# blinds.net
KiCad netlist of a schematic drawn in Altium Designer
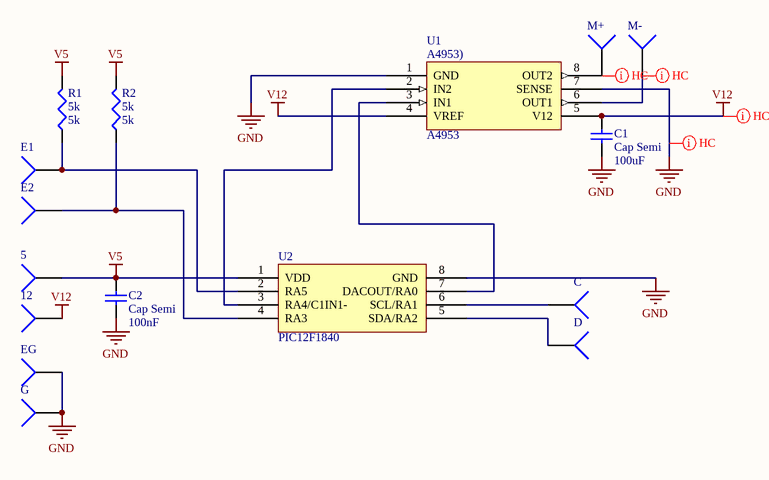
[diagram p0: blinds.SchDoc]

(export (version "E")
  (design (tool "Eeschema 10.0.6"))
  (components
    (comp (ref "5")
      (value "Socket")
      (footprint "PIN1L")
      (fields (field (name "PUBLISHER") "Altium Limited"))
      (libsource (lib "misc") (part "Socket"))
    )
    (comp (ref "12")
      (value "Socket")
      (footprint "PIN1L")
      (fields (field (name "PUBLISHER") "Altium Limited"))
      (libsource (lib "misc") (part "Socket"))
    )
    (comp (ref "C")
      (value "Socket")
      (footprint "PIN1L")
      (fields (field (name "PUBLISHER") "Altium Limited"))
      (libsource (lib "misc") (part "Socket"))
    )
    (comp (ref "C1")
      (value "Cap Semi")
      (footprint "C1206")
      (description "Capacitor (Semiconductor SIM Model)")
      (fields (field (name "ALTIUM_VALUE") "100uF") (field (name "PUBLISHER") "Altium Limited"))
      (libsource (lib "Miscellaneous Devices") (part "Cap Semi"))
    )
    (comp (ref "C2")
      (value "Cap Semi")
      (footprint "1608[0603]")
      (description "Capacitor (Semiconductor SIM Model)")
      (fields (field (name "ALTIUM_VALUE") "100nF") (field (name "PUBLISHER") "Altium Limited"))
      (libsource (lib "Miscellaneous Devices") (part "Cap Semi"))
    )
    (comp (ref "D")
      (value "Socket")
      (footprint "PIN1L")
      (fields (field (name "PUBLISHER") "Altium Limited"))
      (libsource (lib "misc") (part "Socket"))
    )
    (comp (ref "E1")
      (value "Socket")
      (footprint "PIN1L")
      (fields (field (name "PUBLISHER") "Altium Limited"))
      (libsource (lib "misc") (part "Socket"))
    )
    (comp (ref "E2")
      (value "Socket")
      (footprint "PIN1L")
      (fields (field (name "PUBLISHER") "Altium Limited"))
      (libsource (lib "misc") (part "Socket"))
    )
    (comp (ref "EG")
      (value "Socket")
      (footprint "PIN1L")
      (fields (field (name "PUBLISHER") "Altium Limited"))
      (libsource (lib "misc") (part "Socket"))
    )
    (comp (ref "G")
      (value "Socket")
      (footprint "PIN1L")
      (fields (field (name "PUBLISHER") "Altium Limited"))
      (libsource (lib "misc") (part "Socket"))
    )
    (comp (ref "M+")
      (value "Socket")
      (footprint "PIN1L")
      (fields (field (name "PUBLISHER") "Altium Limited"))
      (libsource (lib "misc") (part "Socket"))
    )
    (comp (ref "M-")
      (value "Socket")
      (footprint "PIN1L")
      (fields (field (name "PUBLISHER") "Altium Limited"))
      (libsource (lib "misc") (part "Socket"))
    )
    (comp (ref "R1")
      (value "5k")
      (footprint "J1-0603")
      (description "Resistor")
      (fields (field (name "ALTIUM_VALUE") "5k") (field (name "PUBLISHER") "Altium Limited"))
      (libsource (lib "Miscellaneous Devices") (part "Res3"))
    )
    (comp (ref "R2")
      (value "5k")
      (footprint "J1-0603")
      (description "Resistor")
      (fields (field (name "ALTIUM_VALUE") "5k") (field (name "PUBLISHER") "Altium Limited"))
      (libsource (lib "Miscellaneous Devices") (part "Res3"))
    )
    (comp (ref "U1") (value "A4953") (footprint "SOIC150-8_N") (libsource (lib "misc") (part "A4953")))
    (comp (ref "U2")
      (value "PIC12F1840")
      (footprint "SOIC150-8_N")
      (libsource (lib "pic") (part "PIC12F1840"))
    )
  )
  (nets
    (net (code "1") (name "GND") (class "Default")
      (node (ref "C1") (pin "1") (pinfunction "1_1") (pintype "passive"))
      (node (ref "C2") (pin "1") (pinfunction "1_1") (pintype "passive"))
      (node (ref "EG") (pin "1") (pinfunction "1_1") (pintype "passive"))
      (node (ref "G") (pin "1") (pinfunction "1_1") (pintype "passive"))
      (node (ref "U1") (pin "1") (pinfunction "GND_1") (pintype "passive"))
      (node (ref "U1") (pin "7") (pinfunction "SENSE_7") (pintype "open_emitter"))
      (node (ref "U2") (pin "8") (pinfunction "GND_8") (pintype "passive"))
    )
    (net (code "2") (name "Net-(U1-IN1)") (class "Default")
      (node (ref "U1") (pin "3") (pinfunction "IN1_3") (pintype "input"))
      (node (ref "U2") (pin "7") (pinfunction "DACOUT/RA0_7") (pintype "passive"))
    )
    (net (code "3") (name "Net-(U1-IN2)") (class "Default")
      (node (ref "U1") (pin "2") (pinfunction "IN2_2") (pintype "input"))
      (node (ref "U2") (pin "3") (pinfunction "RA4/C1IN1-_3") (pintype "passive"))
    )
    (net (code "4") (name "Net-(U1-OUT1)") (class "Default")
      (node (ref "M-") (pin "1") (pinfunction "1_1") (pintype "passive"))
      (node (ref "U1") (pin "6") (pinfunction "OUT1_6") (pintype "output"))
    )
    (net (code "5") (name "Net-(U1-OUT2)") (class "Default")
      (node (ref "M+") (pin "1") (pinfunction "1_1") (pintype "passive"))
      (node (ref "U1") (pin "8") (pinfunction "OUT2_8") (pintype "output"))
    )
    (net (code "6") (name "Net-(U2-RA3)") (class "Default")
      (node (ref "E2") (pin "1") (pinfunction "1_1") (pintype "passive"))
      (node (ref "R2") (pin "1") (pinfunction "1_1") (pintype "passive"))
      (node (ref "U2") (pin "4") (pinfunction "RA3_4") (pintype "passive"))
    )
    (net (code "7") (name "Net-(U2-RA5)") (class "Default")
      (node (ref "E1") (pin "1") (pinfunction "1_1") (pintype "passive"))
      (node (ref "R1") (pin "1") (pinfunction "1_1") (pintype "passive"))
      (node (ref "U2") (pin "2") (pinfunction "RA5_2") (pintype "passive"))
    )
    (net (code "8") (name "Net-(U2-SCL{slash}RA1)") (class "Default")
      (node (ref "C") (pin "1") (pinfunction "1_1") (pintype "passive"))
      (node (ref "U2") (pin "6") (pinfunction "SCL/RA1_6") (pintype "passive"))
    )
    (net (code "9") (name "Net-(U2-SDA{slash}RA2)") (class "Default")
      (node (ref "D") (pin "1") (pinfunction "1_1") (pintype "passive"))
      (node (ref "U2") (pin "5") (pinfunction "SDA/RA2_5") (pintype "passive"))
    )
    (net (code "10") (name "V5") (class "Default")
      (node (ref "5") (pin "1") (pinfunction "1_1") (pintype "passive"))
      (node (ref "C2") (pin "2") (pinfunction "2_2") (pintype "passive"))
      (node (ref "R1") (pin "2") (pinfunction "2_2") (pintype "passive"))
      (node (ref "R2") (pin "2") (pinfunction "2_2") (pintype "passive"))
      (node (ref "U2") (pin "1") (pinfunction "VDD_1") (pintype "passive"))
    )
    (net (code "11") (name "V12") (class "Default")
      (node (ref "12") (pin "1") (pinfunction "1_1") (pintype "passive"))
      (node (ref "C1") (pin "2") (pinfunction "2_2") (pintype "passive"))
      (node (ref "U1") (pin "4") (pinfunction "VREF_4") (pintype "power_in"))
      (node (ref "U1") (pin "5") (pinfunction "V12_5") (pintype "power_in"))
    )
  )
)
